# TopPCB.net
KiCad netlist of a schematic drawn in EAGLE
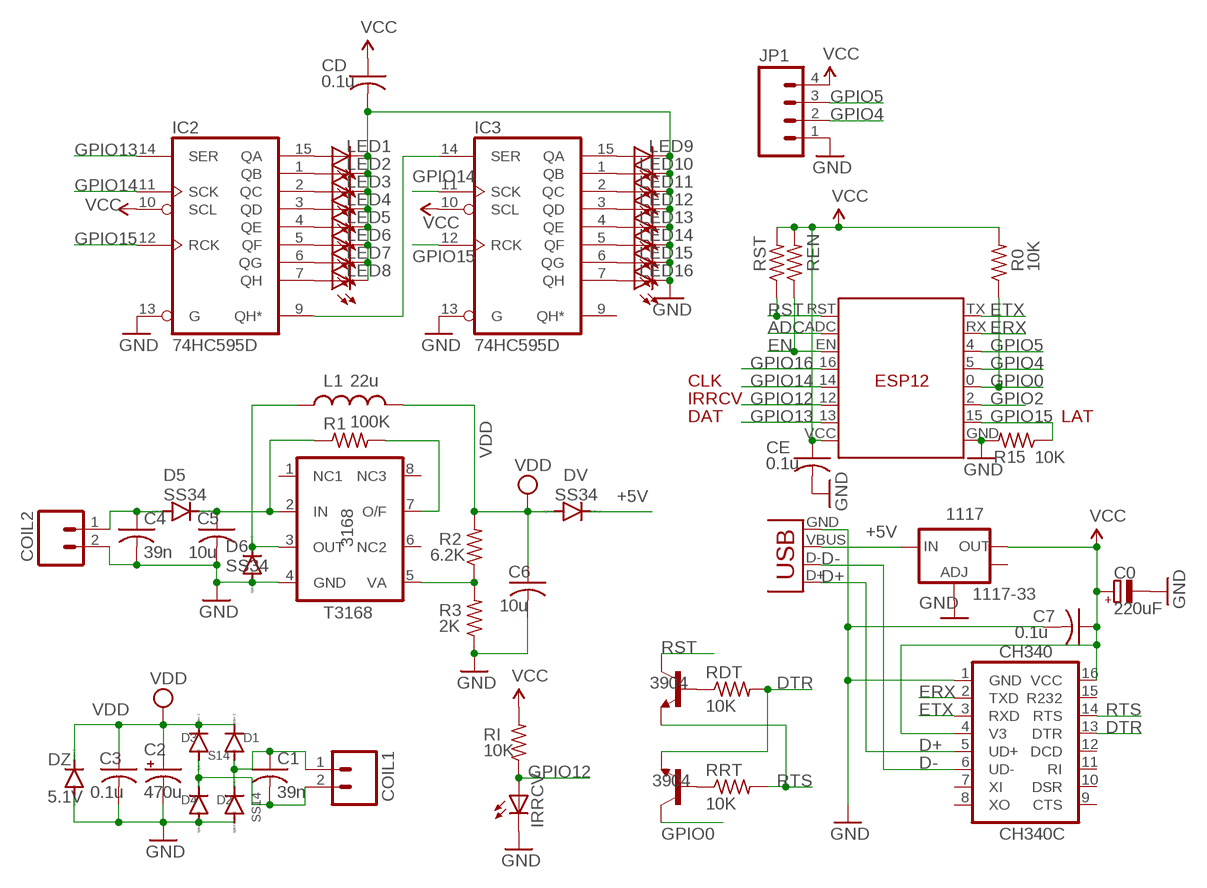
[diagram p0: schematic, sheet 1]

(export (version "E")
  (design (tool "Eeschema 10.0.6"))
  (components
    (comp (ref "1117")
      (value "1117-33")
      (footprint "eagle-import:SOT223")
      (libsource (lib "eagle-import") (part "V_REG_LM1117SOT223"))
    )
    (comp (ref "3168")
      (value "T3168")
      (footprint "eagle-import:SO08")
      (libsource (lib "eagle-import") (part "T3168"))
    )
    (comp (ref "C0")
      (value "220uF")
      (footprint "eagle-import:CT3528")
      (libsource (lib "eagle-import") (part "CPOL-EUCT3528"))
    )
    (comp (ref "C1")
      (value "39n")
      (footprint "eagle-import:C0805K")
      (libsource (lib "eagle-import") (part "adafruit2013_C-USC0805K"))
    )
    (comp (ref "C2")
      (value "470u")
      (footprint "eagle-import:E2,5-6")
      (libsource (lib "eagle-import") (part "CPOL-USE2.5-6"))
    )
    (comp (ref "C3")
      (value "0.1u")
      (footprint "eagle-import:C0805K")
      (libsource (lib "eagle-import") (part "adafruit2013_C-USC0805K"))
    )
    (comp (ref "C4")
      (value "39n")
      (footprint "eagle-import:C0805K")
      (libsource (lib "eagle-import") (part "adafruit2013_C-USC0805K"))
    )
    (comp (ref "C5")
      (value "10u")
      (footprint "eagle-import:C0805K")
      (libsource (lib "eagle-import") (part "adafruit2013_C-USC0805K"))
    )
    (comp (ref "C6")
      (value "10u")
      (footprint "eagle-import:C0805K")
      (libsource (lib "eagle-import") (part "adafruit2013_C-USC0805K"))
    )
    (comp (ref "C7")
      (value "0.1u")
      (footprint "eagle-import:C0603K")
      (libsource (lib "eagle-import") (part "C-USC0603K"))
    )
    (comp (ref "CD")
      (value "0.1u")
      (footprint "eagle-import:C0603K")
      (libsource (lib "eagle-import") (part "C-USC0603K"))
    )
    (comp (ref "CE")
      (value "0.1u")
      (footprint "eagle-import:C0603K")
      (libsource (lib "eagle-import") (part "C-USC0603K"))
    )
    (comp (ref "CH340")
      (value "CH340C")
      (footprint "eagle-import:SO16")
      (libsource (lib "eagle-import") (part "CH340G"))
    )
    (comp (ref "COIL1")
      (value "M021X02_NO_SILK")
      (footprint "eagle-import:1X02_NO_SILK")
      (libsource (lib "eagle-import") (part "M021X02_NO_SILK"))
    )
    (comp (ref "COIL2")
      (value "M021X02_NO_SILK")
      (footprint "eagle-import:1X02_NO_SILK")
      (libsource (lib "eagle-import") (part "M021X02_NO_SILK"))
    )
    (comp (ref "D1")
      (value "S14")
      (footprint "eagle-import:DO-214AC")
      (libsource (lib "eagle-import") (part "DIODE-DO-214AC"))
    )
    (comp (ref "D2")
      (value "SS14")
      (footprint "eagle-import:DO-214AC")
      (libsource (lib "eagle-import") (part "DIODE-DO-214AC"))
    )
    (comp (ref "D3")
      (value "SS14")
      (footprint "eagle-import:DO-214AC")
      (libsource (lib "eagle-import") (part "DIODE-DO-214AC"))
    )
    (comp (ref "D4")
      (value "SS14")
      (footprint "eagle-import:DO-214AC")
      (libsource (lib "eagle-import") (part "DIODE-DO-214AC"))
    )
    (comp (ref "D5")
      (value "SS34")
      (footprint "eagle-import:DO-214AC")
      (libsource (lib "eagle-import") (part "DIODE-DO-214AC"))
    )
    (comp (ref "D6")
      (value "SS34")
      (footprint "eagle-import:DO-214AC")
      (libsource (lib "eagle-import") (part "DIODE-DO-214AC"))
    )
    (comp (ref "DV")
      (value "SS34")
      (footprint "eagle-import:DO-214AC")
      (libsource (lib "eagle-import") (part "DIODE-DO-214AC"))
    )
    (comp (ref "DZ")
      (value "5.1V")
      (footprint "eagle-import:MINIMELF")
      (libsource (lib "eagle-import") (part "DIODE-MINIMELF"))
    )
    (comp (ref "ESP")
      (value "ESP")
      (footprint "eagle-import:ESP12")
      (libsource (lib "eagle-import") (part "ESP12"))
    )
    (comp (ref "IC2")
      (value "74HC595D")
      (footprint "eagle-import:SO16")
      (libsource (lib "eagle-import") (part "74595DHC"))
    )
    (comp (ref "IC3")
      (value "74HC595D")
      (footprint "eagle-import:SO16")
      (libsource (lib "eagle-import") (part "74595DHC"))
    )
    (comp (ref "IRRCV")
      (value "LED3MM")
      (footprint "eagle-import:LED3MM")
      (libsource (lib "eagle-import") (part "LED3MM"))
    )
    (comp (ref "JP1")
      (value "M041X04_NO_SILK")
      (footprint "eagle-import:1X04_NO_SILK")
      (libsource (lib "eagle-import") (part "M041X04_NO_SILK"))
    )
    (comp (ref "L1")
      (value "22u")
      (footprint "eagle-import:CR54")
      (libsource (lib "eagle-import") (part "INDUCTORCR54"))
    )
    (comp (ref "LED1")
      (value "LEDCHIPLED_0805")
      (footprint "eagle-import:CHIPLED_0805")
      (libsource (lib "eagle-import") (part "LEDCHIPLED_0805"))
    )
    (comp (ref "LED2")
      (value "LEDCHIPLED_0805")
      (footprint "eagle-import:CHIPLED_0805")
      (libsource (lib "eagle-import") (part "LEDCHIPLED_0805"))
    )
    (comp (ref "LED3")
      (value "LEDCHIPLED_0805")
      (footprint "eagle-import:CHIPLED_0805")
      (libsource (lib "eagle-import") (part "LEDCHIPLED_0805"))
    )
    (comp (ref "LED4")
      (value "LEDCHIPLED_0805")
      (footprint "eagle-import:CHIPLED_0805")
      (libsource (lib "eagle-import") (part "LEDCHIPLED_0805"))
    )
    (comp (ref "LED5")
      (value "LEDCHIPLED_0805")
      (footprint "eagle-import:CHIPLED_0805")
      (libsource (lib "eagle-import") (part "LEDCHIPLED_0805"))
    )
    (comp (ref "LED6")
      (value "LEDCHIPLED_0805")
      (footprint "eagle-import:CHIPLED_0805")
      (libsource (lib "eagle-import") (part "LEDCHIPLED_0805"))
    )
    (comp (ref "LED7")
      (value "LEDCHIPLED_0805")
      (footprint "eagle-import:CHIPLED_0805")
      (libsource (lib "eagle-import") (part "LEDCHIPLED_0805"))
    )
    (comp (ref "LED8")
      (value "LEDCHIPLED_0805")
      (footprint "eagle-import:CHIPLED_0805")
      (libsource (lib "eagle-import") (part "LEDCHIPLED_0805"))
    )
    (comp (ref "LED9")
      (value "LEDCHIPLED_0805")
      (footprint "eagle-import:CHIPLED_0805")
      (libsource (lib "eagle-import") (part "LEDCHIPLED_0805"))
    )
    (comp (ref "LED10")
      (value "LEDCHIPLED_0805")
      (footprint "eagle-import:CHIPLED_0805")
      (libsource (lib "eagle-import") (part "LEDCHIPLED_0805"))
    )
    (comp (ref "LED11")
      (value "LEDCHIPLED_0805")
      (footprint "eagle-import:CHIPLED_0805")
      (libsource (lib "eagle-import") (part "LEDCHIPLED_0805"))
    )
    (comp (ref "LED12")
      (value "LEDCHIPLED_0805")
      (footprint "eagle-import:CHIPLED_0805")
      (libsource (lib "eagle-import") (part "LEDCHIPLED_0805"))
    )
    (comp (ref "LED13")
      (value "LEDCHIPLED_0805")
      (footprint "eagle-import:CHIPLED_0805")
      (libsource (lib "eagle-import") (part "LEDCHIPLED_0805"))
    )
    (comp (ref "LED14")
      (value "LEDCHIPLED_0805")
      (footprint "eagle-import:CHIPLED_0805")
      (libsource (lib "eagle-import") (part "LEDCHIPLED_0805"))
    )
    (comp (ref "LED15")
      (value "LEDCHIPLED_0805")
      (footprint "eagle-import:CHIPLED_0805")
      (libsource (lib "eagle-import") (part "LEDCHIPLED_0805"))
    )
    (comp (ref "LED16")
      (value "LEDCHIPLED_0805")
      (footprint "eagle-import:CHIPLED_0805")
      (libsource (lib "eagle-import") (part "LEDCHIPLED_0805"))
    )
    (comp (ref "R0")
      (value "10K")
      (footprint "eagle-import:R0603")
      (libsource (lib "eagle-import") (part "adafruit (picker 的冲突副本 2014-10-29)_R-US_R0603"))
    )
    (comp (ref "R1")
      (value "100K")
      (footprint "eagle-import:R0603")
      (libsource (lib "eagle-import") (part "R-US_R0603"))
    )
    (comp (ref "R2")
      (value "6.2K")
      (footprint "eagle-import:R0603")
      (libsource (lib "eagle-import") (part "R-US_R0603"))
    )
    (comp (ref "R3")
      (value "2K")
      (footprint "eagle-import:R0603")
      (libsource (lib "eagle-import") (part "R-US_R0603"))
    )
    (comp (ref "R15")
      (value "10K")
      (footprint "eagle-import:R0603")
      (libsource (lib "eagle-import") (part "adafruit (picker 的冲突副本 2014-10-29)_R-US_R0603"))
    )
    (comp (ref "RDT")
      (value "10K")
      (footprint "eagle-import:R0603")
      (libsource (lib "eagle-import") (part "adafruit2013_R-US_R0603"))
    )
    (comp (ref "REN")
      (value "10K")
      (footprint "eagle-import:R0603")
      (libsource (lib "eagle-import") (part "adafruit (picker 的冲突副本 2014-10-29)_R-US_R0603"))
    )
    (comp (ref "RI")
      (value "10K")
      (footprint "eagle-import:R0603")
      (libsource (lib "eagle-import") (part "R-US_R0603"))
    )
    (comp (ref "RRT")
      (value "10K")
      (footprint "eagle-import:R0603")
      (libsource (lib "eagle-import") (part "adafruit2013_R-US_R0603"))
    )
    (comp (ref "RST")
      (value "10K")
      (footprint "eagle-import:R0603")
      (libsource (lib "eagle-import") (part "adafruit (picker 的冲突副本 2014-10-29)_R-US_R0603"))
    )
    (comp (ref "T1")
      (value "3904")
      (footprint "eagle-import:SOT23-BEC")
      (libsource (lib "eagle-import") (part "-NPN-SOT23-BECMMBT3904LT1"))
    )
    (comp (ref "T2")
      (value "3904")
      (footprint "eagle-import:SOT23-BEC")
      (libsource (lib "eagle-import") (part "-NPN-SOT23-BECMMBT3904LT1"))
    )
    (comp (ref "X3")
      (value "USBMICROB2")
      (footprint "eagle-import:USB-MICROB2")
      (libsource (lib "eagle-import") (part "USBMICROB2"))
    )
  )
  (nets
    (net (code "1") (name "/+5V") (class "Default")
      (node (ref "1117") (pin "3") (pinfunction "IN_3") (pintype "input"))
      (node (ref "DV") (pin "C") (pinfunction "C_C") (pintype "passive"))
      (node (ref "X3") (pin "VBUS") (pinfunction "VBUS_VBUS") (pintype "bidirectional"))
    )
    (net (code "2") (name "/ADC") (class "Default")
      (node (ref "ESP") (pin "ADC") (pinfunction "ADC_ADC") (pintype "bidirectional"))
    )
    (net (code "3") (name "/D+") (class "Default")
      (node (ref "CH340") (pin "5") (pinfunction "UD+_5") (pintype "bidirectional"))
      (node (ref "X3") (pin "D+") (pinfunction "D+_D+") (pintype "bidirectional"))
    )
    (net (code "4") (name "/D-") (class "Default")
      (node (ref "CH340") (pin "6") (pinfunction "UD-_6") (pintype "bidirectional"))
      (node (ref "X3") (pin "D-") (pinfunction "D-_D-") (pintype "bidirectional"))
    )
    (net (code "5") (name "/DTR") (class "Default")
      (node (ref "CH340") (pin "13") (pinfunction "DTR_13") (pintype "bidirectional"))
      (node (ref "RDT") (pin "2") (pinfunction "2_2") (pintype "passive"))
      (node (ref "T2") (pin "E") (pinfunction "E_E") (pintype "passive"))
    )
    (net (code "6") (name "/EN") (class "Default")
      (node (ref "ESP") (pin "EN") (pinfunction "EN_EN") (pintype "bidirectional"))
      (node (ref "REN") (pin "1") (pinfunction "1_1") (pintype "passive"))
    )
    (net (code "7") (name "/ERX") (class "Default")
      (node (ref "CH340") (pin "2") (pinfunction "TXD_2") (pintype "bidirectional"))
      (node (ref "ESP") (pin "RX") (pinfunction "RX_RX") (pintype "bidirectional"))
    )
    (net (code "8") (name "/ETX") (class "Default")
      (node (ref "CH340") (pin "3") (pinfunction "RXD_3") (pintype "bidirectional"))
      (node (ref "ESP") (pin "TX") (pinfunction "TX_TX") (pintype "bidirectional"))
    )
    (net (code "9") (name "/GPIO0") (class "Default")
      (node (ref "ESP") (pin "0") (pinfunction "G0_0") (pintype "bidirectional"))
      (node (ref "R0") (pin "1") (pinfunction "1_1") (pintype "passive"))
      (node (ref "T2") (pin "C") (pinfunction "C_C") (pintype "passive"))
    )
    (net (code "10") (name "/GPIO2") (class "Default")
      (node (ref "ESP") (pin "2") (pinfunction "G2_2") (pintype "bidirectional"))
    )
    (net (code "11") (name "/GPIO4") (class "Default")
      (node (ref "ESP") (pin "5") (pinfunction "G5_5") (pintype "bidirectional"))
      (node (ref "JP1") (pin "2") (pinfunction "2_2") (pintype "passive"))
    )
    (net (code "12") (name "/GPIO5") (class "Default")
      (node (ref "ESP") (pin "4") (pinfunction "G4_4") (pintype "bidirectional"))
      (node (ref "JP1") (pin "3") (pinfunction "3_3") (pintype "passive"))
    )
    (net (code "13") (name "/GPIO12") (class "Default")
      (node (ref "ESP") (pin "12") (pinfunction "G12_12") (pintype "bidirectional"))
      (node (ref "IRRCV") (pin "A") (pinfunction "A_A") (pintype "passive"))
      (node (ref "RI") (pin "1") (pinfunction "1_1") (pintype "passive"))
    )
    (net (code "14") (name "/GPIO13") (class "Default")
      (node (ref "ESP") (pin "13") (pinfunction "G13_13") (pintype "bidirectional"))
      (node (ref "IC2") (pin "14") (pinfunction "SER_14") (pintype "input"))
    )
    (net (code "15") (name "/GPIO14") (class "Default")
      (node (ref "ESP") (pin "14") (pinfunction "G14_14") (pintype "bidirectional"))
      (node (ref "IC2") (pin "11") (pinfunction "SCK_11") (pintype "input"))
      (node (ref "IC3") (pin "11") (pinfunction "SCK_11") (pintype "input"))
    )
    (net (code "16") (name "/GPIO15") (class "Default")
      (node (ref "ESP") (pin "15") (pinfunction "G15_15") (pintype "bidirectional"))
      (node (ref "IC2") (pin "12") (pinfunction "RCK_12") (pintype "input"))
      (node (ref "IC3") (pin "12") (pinfunction "RCK_12") (pintype "input"))
      (node (ref "R15") (pin "1") (pinfunction "1_1") (pintype "passive"))
    )
    (net (code "17") (name "/GPIO16") (class "Default")
      (node (ref "ESP") (pin "16") (pinfunction "G16_16") (pintype "bidirectional"))
    )
    (net (code "18") (name "/RST") (class "Default")
      (node (ref "ESP") (pin "RST") (pinfunction "RST_RST") (pintype "bidirectional"))
      (node (ref "RST") (pin "1") (pinfunction "1_1") (pintype "passive"))
      (node (ref "T1") (pin "C") (pinfunction "C_C") (pintype "passive"))
    )
    (net (code "19") (name "/RTS") (class "Default")
      (node (ref "CH340") (pin "14") (pinfunction "RTS_14") (pintype "bidirectional"))
      (node (ref "RRT") (pin "2") (pinfunction "2_2") (pintype "passive"))
      (node (ref "T1") (pin "E") (pinfunction "E_E") (pintype "passive"))
    )
    (net (code "20") (name "GND") (class "Default")
      (node (ref "1117") (pin "1") (pinfunction "ADJ_1") (pintype "input"))
      (node (ref "3168") (pin "4") (pinfunction "GND_4") (pintype "power_in"))
      (node (ref "C0") (pin "-") (pinfunction "-_-") (pintype "passive"))
      (node (ref "C2") (pin "-") (pinfunction "-_-") (pintype "passive"))
      (node (ref "C3") (pin "2") (pinfunction "2_2") (pintype "passive"))
      (node (ref "C4") (pin "2") (pinfunction "2_2") (pintype "passive"))
      (node (ref "C5") (pin "2") (pinfunction "2_2") (pintype "passive"))
      (node (ref "C6") (pin "2") (pinfunction "2_2") (pintype "passive"))
      (node (ref "C7") (pin "2") (pinfunction "2_2") (pintype "passive"))
      (node (ref "CD") (pin "2") (pinfunction "2_2") (pintype "passive"))
      (node (ref "CE") (pin "2") (pinfunction "2_2") (pintype "passive"))
      (node (ref "CH340") (pin "1") (pinfunction "GND_1") (pintype "power_in"))
      (node (ref "COIL2") (pin "2") (pinfunction "2_2") (pintype "passive"))
      (node (ref "D2") (pin "A") (pinfunction "A_A") (pintype "passive"))
      (node (ref "D4") (pin "A") (pinfunction "A_A") (pintype "passive"))
      (node (ref "D6") (pin "A") (pinfunction "A_A") (pintype "passive"))
      (node (ref "DZ") (pin "A") (pinfunction "A_A") (pintype "passive"))
      (node (ref "ESP") (pin "GND") (pinfunction "GND_GND") (pintype "power_in"))
      (node (ref "IC2") (pin "13") (pinfunction "G_13") (pintype "input"))
      (node (ref "IC3") (pin "13") (pinfunction "G_13") (pintype "input"))
      (node (ref "IRRCV") (pin "K") (pinfunction "C_K") (pintype "passive"))
      (node (ref "JP1") (pin "1") (pinfunction "1_1") (pintype "passive"))
      (node (ref "LED1") (pin "C") (pinfunction "C_C") (pintype "passive"))
      (node (ref "LED10") (pin "C") (pinfunction "C_C") (pintype "passive"))
      (node (ref "LED11") (pin "C") (pinfunction "C_C") (pintype "passive"))
      (node (ref "LED12") (pin "C") (pinfunction "C_C") (pintype "passive"))
      (node (ref "LED13") (pin "C") (pinfunction "C_C") (pintype "passive"))
      (node (ref "LED14") (pin "C") (pinfunction "C_C") (pintype "passive"))
      (node (ref "LED15") (pin "C") (pinfunction "C_C") (pintype "passive"))
      (node (ref "LED16") (pin "C") (pinfunction "C_C") (pintype "passive"))
      (node (ref "LED2") (pin "C") (pinfunction "C_C") (pintype "passive"))
      (node (ref "LED3") (pin "C") (pinfunction "C_C") (pintype "passive"))
      (node (ref "LED4") (pin "C") (pinfunction "C_C") (pintype "passive"))
      (node (ref "LED5") (pin "C") (pinfunction "C_C") (pintype "passive"))
      (node (ref "LED6") (pin "C") (pinfunction "C_C") (pintype "passive"))
      (node (ref "LED7") (pin "C") (pinfunction "C_C") (pintype "passive"))
      (node (ref "LED8") (pin "C") (pinfunction "C_C") (pintype "passive"))
      (node (ref "LED9") (pin "C") (pinfunction "C_C") (pintype "passive"))
      (node (ref "R15") (pin "2") (pinfunction "2_2") (pintype "passive"))
      (node (ref "R3") (pin "1") (pinfunction "1_1") (pintype "passive"))
      (node (ref "X3") (pin "GND") (pinfunction "GND_GND") (pintype "bidirectional"))
    )
    (net (code "21") (name "Net-(3168-IN)") (class "Default")
      (node (ref "3168") (pin "2") (pinfunction "IN_2") (pintype "bidirectional"))
      (node (ref "C5") (pin "1") (pinfunction "1_1") (pintype "passive"))
      (node (ref "D5") (pin "C") (pinfunction "C_C") (pintype "passive"))
      (node (ref "R1") (pin "1") (pinfunction "1_1") (pintype "passive"))
    )
    (net (code "22") (name "Net-(3168-OUT)") (class "Default")
      (node (ref "3168") (pin "3") (pinfunction "OUT_3") (pintype "bidirectional"))
      (node (ref "D6") (pin "C") (pinfunction "C_C") (pintype "passive"))
      (node (ref "L1") (pin "P$1") (pinfunction "1_P$1") (pintype "passive"))
    )
    (net (code "23") (name "Net-(3168-O{slash}F)") (class "Default")
      (node (ref "3168") (pin "7") (pinfunction "O/F_7") (pintype "bidirectional"))
      (node (ref "R1") (pin "2") (pinfunction "2_2") (pintype "passive"))
    )
    (net (code "24") (name "Net-(3168-VA)") (class "Default")
      (node (ref "3168") (pin "5") (pinfunction "VA_5") (pintype "bidirectional"))
      (node (ref "R2") (pin "1") (pinfunction "1_1") (pintype "passive"))
      (node (ref "R3") (pin "2") (pinfunction "2_2") (pintype "passive"))
    )
    (net (code "25") (name "Net-(C1-Pad1)") (class "Default")
      (node (ref "C1") (pin "1") (pinfunction "1_1") (pintype "passive"))
      (node (ref "COIL1") (pin "1") (pinfunction "1_1") (pintype "passive"))
      (node (ref "D1") (pin "A") (pinfunction "A_A") (pintype "passive"))
      (node (ref "D2") (pin "C") (pinfunction "C_C") (pintype "passive"))
    )
    (net (code "26") (name "Net-(C1-Pad2)") (class "Default")
      (node (ref "C1") (pin "2") (pinfunction "2_2") (pintype "passive"))
      (node (ref "COIL1") (pin "2") (pinfunction "2_2") (pintype "passive"))
      (node (ref "D3") (pin "A") (pinfunction "A_A") (pintype "passive"))
      (node (ref "D4") (pin "C") (pinfunction "C_C") (pintype "passive"))
    )
    (net (code "27") (name "Net-(C4-Pad1)") (class "Default")
      (node (ref "C4") (pin "1") (pinfunction "1_1") (pintype "passive"))
      (node (ref "COIL2") (pin "1") (pinfunction "1_1") (pintype "passive"))
      (node (ref "D5") (pin "A") (pinfunction "A_A") (pintype "passive"))
    )
    (net (code "28") (name "Net-(IC2A-QA)") (class "Default")
      (node (ref "IC2") (pin "15") (pinfunction "QA_15") (pintype "tri_state"))
      (node (ref "LED1") (pin "A") (pinfunction "A_A") (pintype "passive"))
    )
    (net (code "29") (name "Net-(IC2A-QB)") (class "Default")
      (node (ref "IC2") (pin "1") (pinfunction "QB_1") (pintype "tri_state"))
      (node (ref "LED2") (pin "A") (pinfunction "A_A") (pintype "passive"))
    )
    (net (code "30") (name "Net-(IC2A-QC)") (class "Default")
      (node (ref "IC2") (pin "2") (pinfunction "QC_2") (pintype "tri_state"))
      (node (ref "LED3") (pin "A") (pinfunction "A_A") (pintype "passive"))
    )
    (net (code "31") (name "Net-(IC2A-QD)") (class "Default")
      (node (ref "IC2") (pin "3") (pinfunction "QD_3") (pintype "tri_state"))
      (node (ref "LED4") (pin "A") (pinfunction "A_A") (pintype "passive"))
    )
    (net (code "32") (name "Net-(IC2A-QE)") (class "Default")
      (node (ref "IC2") (pin "4") (pinfunction "QE_4") (pintype "tri_state"))
      (node (ref "LED5") (pin "A") (pinfunction "A_A") (pintype "passive"))
    )
    (net (code "33") (name "Net-(IC2A-QF)") (class "Default")
      (node (ref "IC2") (pin "5") (pinfunction "QF_5") (pintype "tri_state"))
      (node (ref "LED6") (pin "A") (pinfunction "A_A") (pintype "passive"))
    )
    (net (code "34") (name "Net-(IC2A-QG)") (class "Default")
      (node (ref "IC2") (pin "6") (pinfunction "QG_6") (pintype "tri_state"))
      (node (ref "LED7") (pin "A") (pinfunction "A_A") (pintype "passive"))
    )
    (net (code "35") (name "Net-(IC2A-QH)") (class "Default")
      (node (ref "IC2") (pin "7") (pinfunction "QH_7") (pintype "tri_state"))
      (node (ref "LED8") (pin "A") (pinfunction "A_A") (pintype "passive"))
    )
    (net (code "36") (name "Net-(IC2A-QH*)") (class "Default")
      (node (ref "IC2") (pin "9") (pinfunction "QH*_9") (pintype "tri_state"))
      (node (ref "IC3") (pin "14") (pinfunction "SER_14") (pintype "input"))
    )
    (net (code "37") (name "Net-(IC3A-QA)") (class "Default")
      (node (ref "IC3") (pin "15") (pinfunction "QA_15") (pintype "tri_state"))
      (node (ref "LED9") (pin "A") (pinfunction "A_A") (pintype "passive"))
    )
    (net (code "38") (name "Net-(IC3A-QB)") (class "Default")
      (node (ref "IC3") (pin "1") (pinfunction "QB_1") (pintype "tri_state"))
      (node (ref "LED10") (pin "A") (pinfunction "A_A") (pintype "passive"))
    )
    (net (code "39") (name "Net-(IC3A-QC)") (class "Default")
      (node (ref "IC3") (pin "2") (pinfunction "QC_2") (pintype "tri_state"))
      (node (ref "LED11") (pin "A") (pinfunction "A_A") (pintype "passive"))
    )
    (net (code "40") (name "Net-(IC3A-QD)") (class "Default")
      (node (ref "IC3") (pin "3") (pinfunction "QD_3") (pintype "tri_state"))
      (node (ref "LED12") (pin "A") (pinfunction "A_A") (pintype "passive"))
    )
    (net (code "41") (name "Net-(IC3A-QE)") (class "Default")
      (node (ref "IC3") (pin "4") (pinfunction "QE_4") (pintype "tri_state"))
      (node (ref "LED13") (pin "A") (pinfunction "A_A") (pintype "passive"))
    )
    (net (code "42") (name "Net-(IC3A-QF)") (class "Default")
      (node (ref "IC3") (pin "5") (pinfunction "QF_5") (pintype "tri_state"))
      (node (ref "LED14") (pin "A") (pinfunction "A_A") (pintype "passive"))
    )
    (net (code "43") (name "Net-(IC3A-QG)") (class "Default")
      (node (ref "IC3") (pin "6") (pinfunction "QG_6") (pintype "tri_state"))
      (node (ref "LED15") (pin "A") (pinfunction "A_A") (pintype "passive"))
    )
    (net (code "44") (name "Net-(IC3A-QH)") (class "Default")
      (node (ref "IC3") (pin "7") (pinfunction "QH_7") (pintype "tri_state"))
      (node (ref "LED16") (pin "A") (pinfunction "A_A") (pintype "passive"))
    )
    (net (code "45") (name "Net-(RDT-Pad1)") (class "Default")
      (node (ref "RDT") (pin "1") (pinfunction "1_1") (pintype "passive"))
      (node (ref "T1") (pin "B") (pinfunction "B_B") (pintype "passive"))
    )
    (net (code "46") (name "Net-(RRT-Pad1)") (class "Default")
      (node (ref "RRT") (pin "1") (pinfunction "1_1") (pintype "passive"))
      (node (ref "T2") (pin "B") (pinfunction "B_B") (pintype "passive"))
    )
    (net (code "47") (name "VCC") (class "Default")
      (node (ref "1117") (pin "2") (pinfunction "OUT_2") (pintype "bidirectional"))
      (node (ref "C0") (pin "+") (pinfunction "+_+") (pintype "passive"))
      (node (ref "C7") (pin "1") (pinfunction "1_1") (pintype "passive"))
      (node (ref "CD") (pin "1") (pinfunction "1_1") (pintype "passive"))
      (node (ref "CE") (pin "1") (pinfunction "1_1") (pintype "passive"))
      (node (ref "CH340") (pin "16") (pinfunction "VCC_16") (pintype "power_in"))
      (node (ref "CH340") (pin "4") (pinfunction "V3_4") (pintype "bidirectional"))
      (node (ref "ESP") (pin "VCC") (pinfunction "VCC_VCC") (pintype "power_in"))
      (node (ref "IC2") (pin "10") (pinfunction "SCL_10") (pintype "input"))
      (node (ref "IC3") (pin "10") (pinfunction "SCL_10") (pintype "input"))
      (node (ref "JP1") (pin "4") (pinfunction "4_4") (pintype "passive"))
      (node (ref "R0") (pin "2") (pinfunction "2_2") (pintype "passive"))
      (node (ref "REN") (pin "2") (pinfunction "2_2") (pintype "passive"))
      (node (ref "RI") (pin "2") (pinfunction "2_2") (pintype "passive"))
      (node (ref "RST") (pin "2") (pinfunction "2_2") (pintype "passive"))
    )
    (net (code "48") (name "VDD") (class "Default")
      (node (ref "C2") (pin "+") (pinfunction "+_+") (pintype "passive"))
      (node (ref "C3") (pin "1") (pinfunction "1_1") (pintype "passive"))
      (node (ref "C6") (pin "1") (pinfunction "1_1") (pintype "passive"))
      (node (ref "D1") (pin "C") (pinfunction "C_C") (pintype "passive"))
      (node (ref "D3") (pin "C") (pinfunction "C_C") (pintype "passive"))
      (node (ref "DV") (pin "A") (pinfunction "A_A") (pintype "passive"))
      (node (ref "DZ") (pin "C") (pinfunction "C_C") (pintype "passive"))
      (node (ref "L1") (pin "P$2") (pinfunction "2_P$2") (pintype "passive"))
      (node (ref "R2") (pin "2") (pinfunction "2_2") (pintype "passive"))
    )
    (net (code "49") (name "unconnected-(1117-OUT-Pad4)") (class "Default")
      (node (ref "1117") (pin "4") (pinfunction "OUT_4") (pintype "bidirectional"))
    )
    (net (code "50") (name "unconnected-(3168-NC1-Pad1)") (class "Default")
      (node (ref "3168") (pin "1") (pinfunction "NC1_1") (pintype "bidirectional"))
    )
    (net (code "51") (name "unconnected-(3168-NC2-Pad6)") (class "Default")
      (node (ref "3168") (pin "6") (pinfunction "NC2_6") (pintype "bidirectional"))
    )
    (net (code "52") (name "unconnected-(3168-NC3-Pad8)") (class "Default")
      (node (ref "3168") (pin "8") (pinfunction "NC3_8") (pintype "bidirectional"))
    )
    (net (code "53") (name "unconnected-(CH340-CTS-Pad9)") (class "Default")
      (node (ref "CH340") (pin "9") (pinfunction "CTS_9") (pintype "bidirectional"))
    )
    (net (code "54") (name "unconnected-(CH340-DCD-Pad12)") (class "Default")
      (node (ref "CH340") (pin "12") (pinfunction "DCD_12") (pintype "bidirectional"))
    )
    (net (code "55") (name "unconnected-(CH340-DSR-Pad10)") (class "Default")
      (node (ref "CH340") (pin "10") (pinfunction "DSR_10") (pintype "bidirectional"))
    )
    (net (code "56") (name "unconnected-(CH340-R232-Pad15)") (class "Default")
      (node (ref "CH340") (pin "15") (pinfunction "R232_15") (pintype "bidirectional"))
    )
    (net (code "57") (name "unconnected-(CH340-RI-Pad11)") (class "Default")
      (node (ref "CH340") (pin "11") (pinfunction "RI_11") (pintype "bidirectional"))
    )
    (net (code "58") (name "unconnected-(CH340-XI-Pad7)") (class "Default")
      (node (ref "CH340") (pin "7") (pinfunction "XI_7") (pintype "bidirectional"))
    )
    (net (code "59") (name "unconnected-(CH340-XO-Pad8)") (class "Default")
      (node (ref "CH340") (pin "8") (pinfunction "XO_8") (pintype "bidirectional"))
    )
    (net (code "60") (name "unconnected-(IC3A-QH*-Pad9)") (class "Default")
      (node (ref "IC3") (pin "9") (pinfunction "QH*_9") (pintype "tri_state"))
    )
  )
)
